# 05_-_PCIE_MINI_2_AUDIO2.net
KiCad netlist of a schematic drawn in Altium Designer
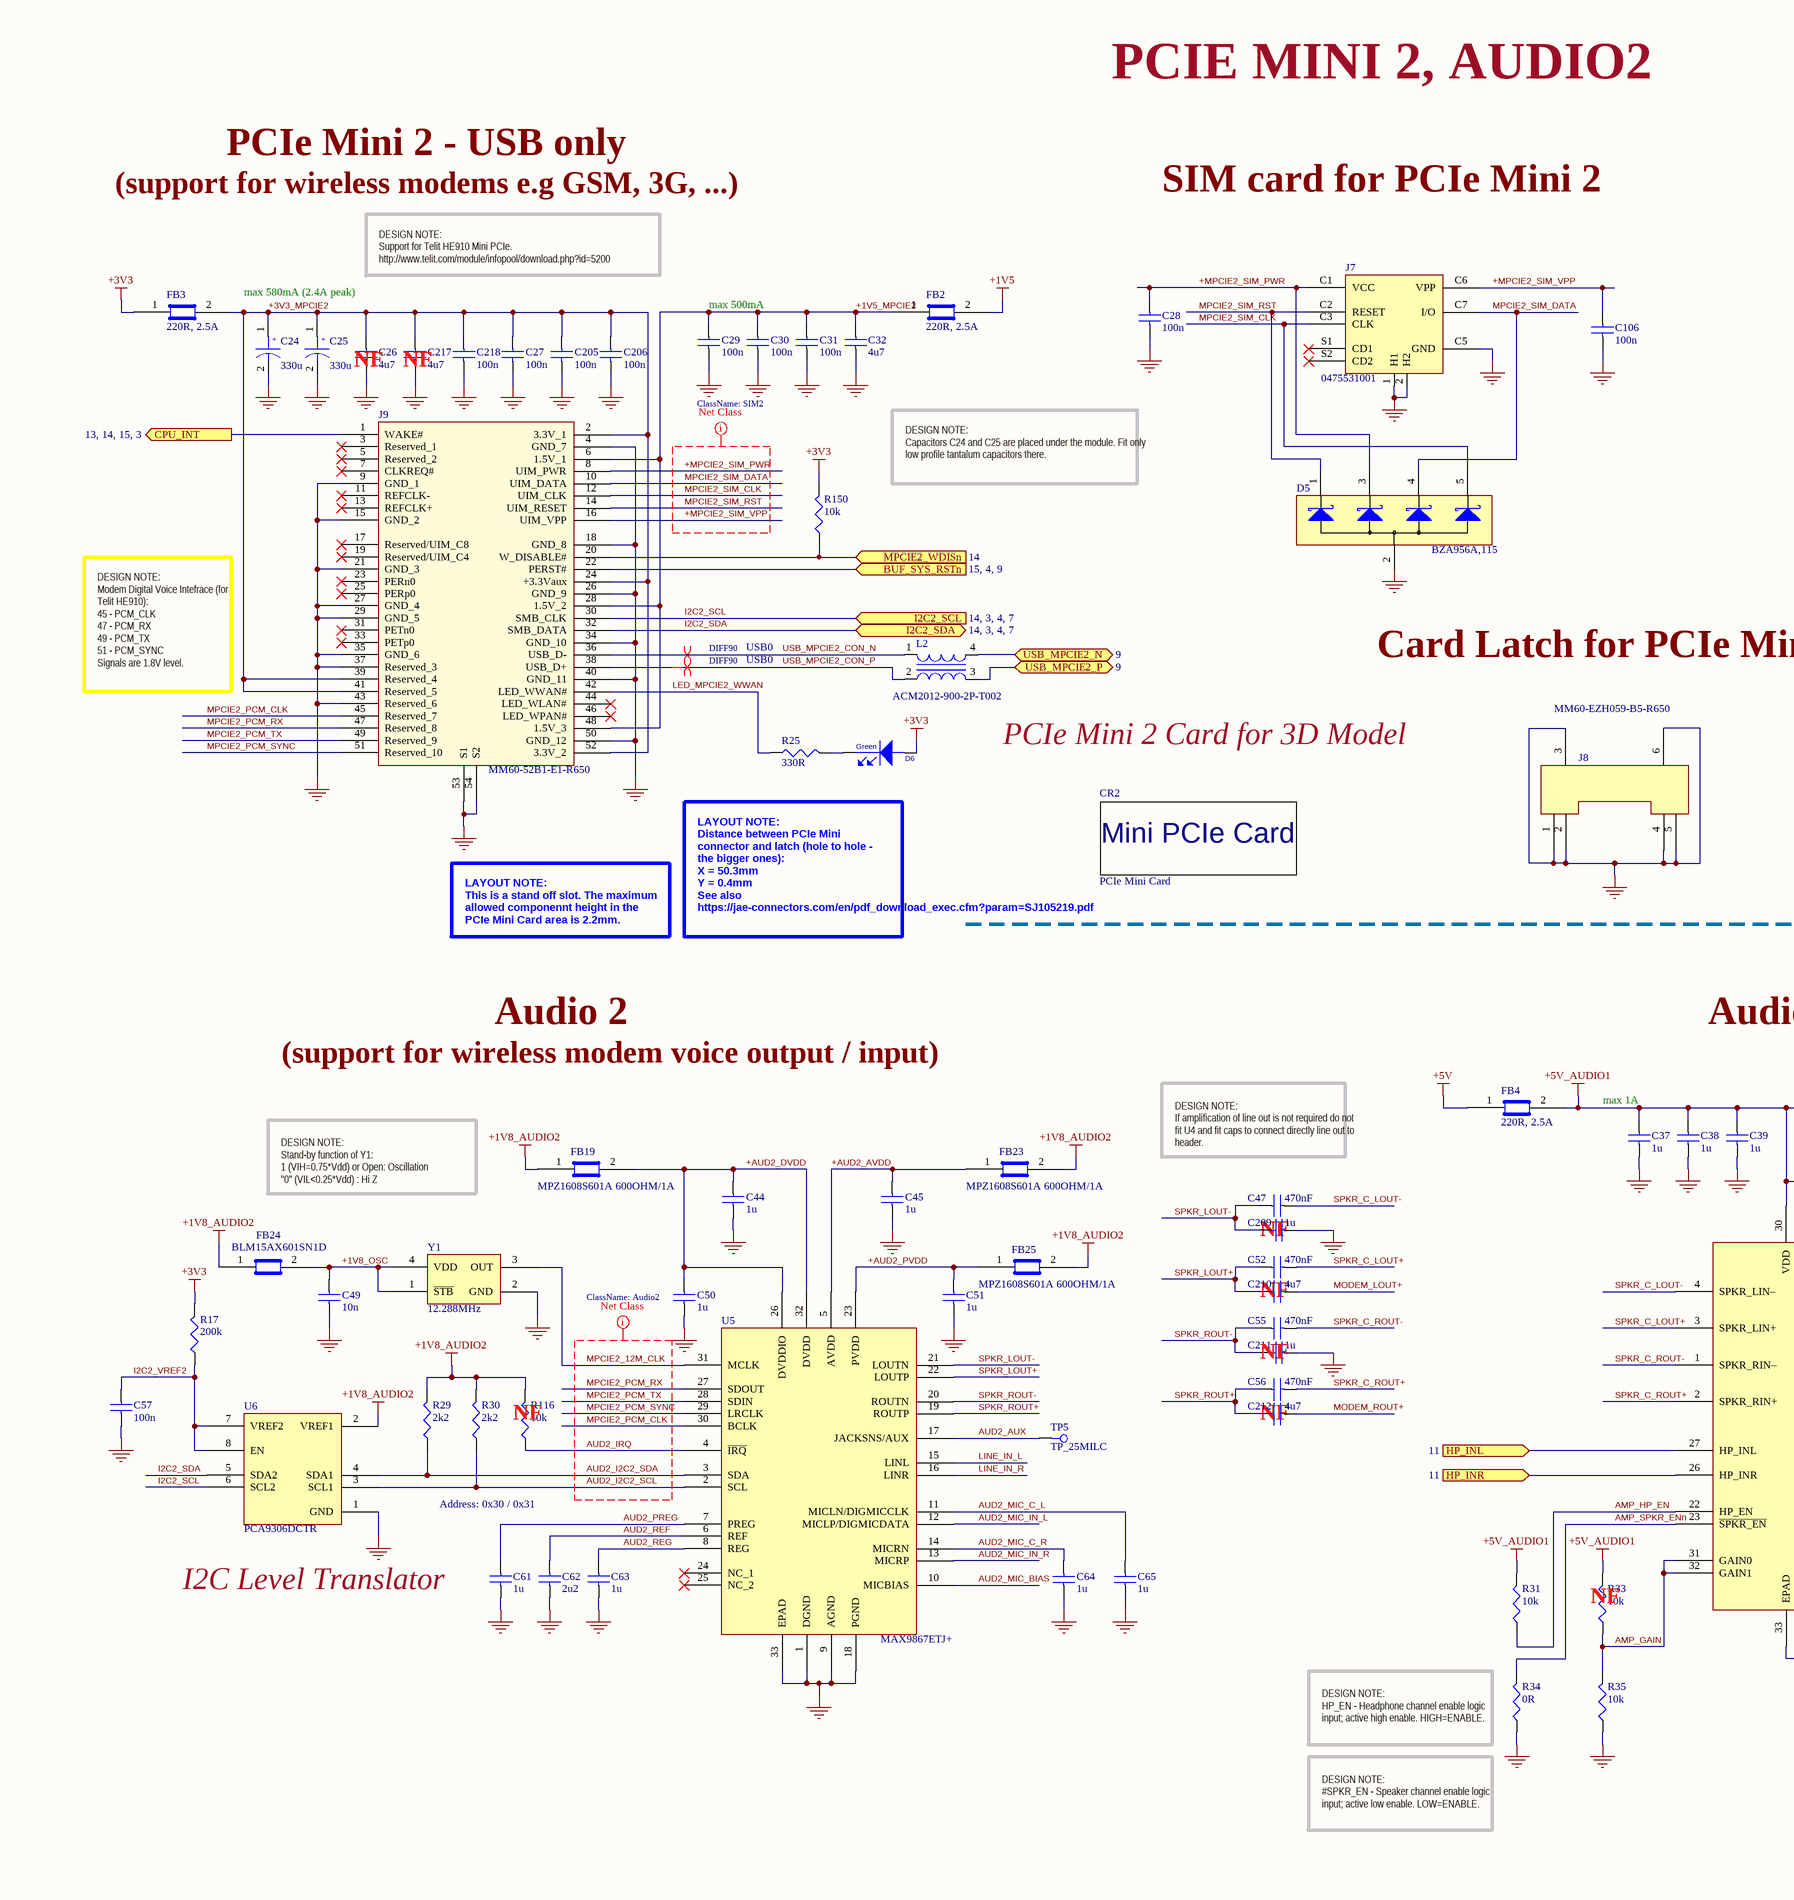
[diagram p0: [05] - PCIE MINI 2, AUDIO2.SchDoc, left]
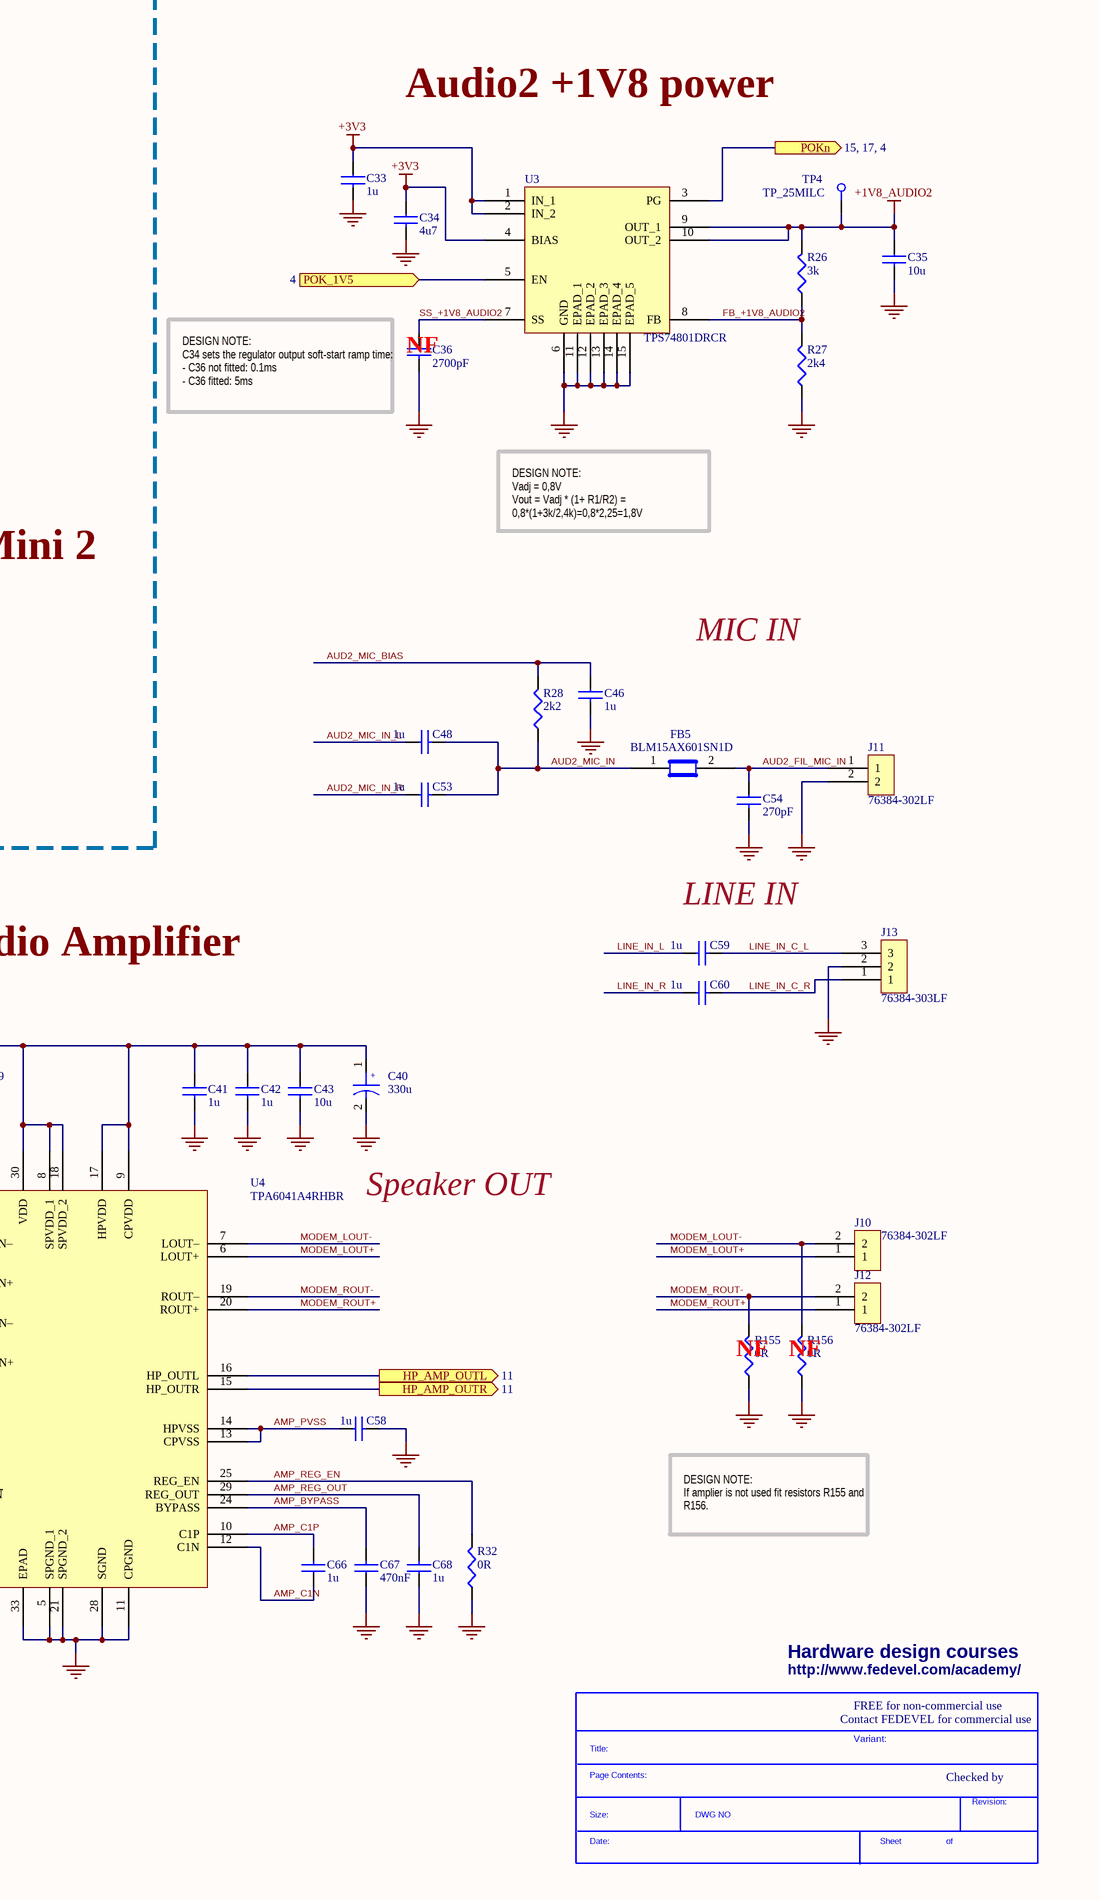
[diagram p1: [05] - PCIE MINI 2, AUDIO2.SchDoc, right]

(export (version "E")
  (design (tool "Eeschema 10.0.6"))
  (components
    (comp (ref "C24")
      (value "330u")
      (footprint "C2917")
      (description "CAP TANT 330UF 6.3V 20% 2917")
      (fields
        (field (name "MANUFACTURER") "Kemet")
        (field (name "MANUFACTURER PART NUMBER") "T520D337M006ATE045")
        (field (name ".CREATOR") "MM")
        (field (name ".CHECKED PCB") "MM")
        (field (name ".CHECKED SCH") "RF, used by MM")
      )
      (libsource (lib "Integrated_Library_RF_FEB_2012") (part "T520D337M006ATE045"))
    )
    (comp (ref "C25")
      (value "330u")
      (footprint "C2917")
      (description "CAP TANT 330UF 6.3V 20% 2917")
      (fields
        (field (name "MANUFACTURER") "Kemet")
        (field (name "MANUFACTURER PART NUMBER") "T520D337M006ATE045")
        (field (name ".CREATOR") "MM")
        (field (name ".CHECKED PCB") "MM")
        (field (name ".CHECKED SCH") "RF, used by MM")
      )
      (libsource (lib "Integrated_Library_RF_FEB_2012") (part "T520D337M006ATE045"))
    )
    (comp (ref "C26")
      (value "4u7")
      (footprint "C0402")
      (description "CAP CER 4.7UF 10V 20% X5R 0402")
      (fields
        (field (name "MANUFACTURER") "TDK Corporation")
        (field (name "MANUFACTURER PART NUMBER") "C1005X5R1A475M")
        (field (name ".CHECKED PCB") "RF")
        (field (name ".CHECKED SCH") "RF")
      )
      (libsource (lib "Integrated_Library_RF_FEB_2012") (part "C1005X5R1A475M"))
    )
    (comp (ref "C27")
      (value "100n")
      (footprint "C0402")
      (description "CAP CER .10UF 50V X5R 10% 0402")
      (fields
        (field (name "MANUFACTURER") "TDK Corporation")
        (field (name "MANUFACTURER PART NUMBER") "C1005X5R1H104K")
      )
      (libsource (lib "Integrated_Library_RF_FEB_2012") (part "C1005X5R1H104K"))
    )
    (comp (ref "C28")
      (value "100n")
      (footprint "C0402")
      (description "CAP CER .10UF 50V X5R 10% 0402")
      (fields
        (field (name "MANUFACTURER") "TDK Corporation")
        (field (name "MANUFACTURER PART NUMBER") "C1005X5R1H104K")
      )
      (libsource (lib "Integrated_Library_RF_FEB_2012") (part "C1005X5R1H104K"))
    )
    (comp (ref "C29")
      (value "100n")
      (footprint "C0402")
      (description "CAP CER .10UF 50V X5R 10% 0402")
      (fields
        (field (name "MANUFACTURER") "TDK Corporation")
        (field (name "MANUFACTURER PART NUMBER") "C1005X5R1H104K")
      )
      (libsource (lib "Integrated_Library_RF_FEB_2012") (part "C1005X5R1H104K"))
    )
    (comp (ref "C30")
      (value "100n")
      (footprint "C0402")
      (description "CAP CER .10UF 50V X5R 10% 0402")
      (fields
        (field (name "MANUFACTURER") "TDK Corporation")
        (field (name "MANUFACTURER PART NUMBER") "C1005X5R1H104K")
      )
      (libsource (lib "Integrated_Library_RF_FEB_2012") (part "C1005X5R1H104K"))
    )
    (comp (ref "C31")
      (value "100n")
      (footprint "C0402")
      (description "CAP CER .10UF 50V X5R 10% 0402")
      (fields
        (field (name "MANUFACTURER") "TDK Corporation")
        (field (name "MANUFACTURER PART NUMBER") "C1005X5R1H104K")
      )
      (libsource (lib "Integrated_Library_RF_FEB_2012") (part "C1005X5R1H104K"))
    )
    (comp (ref "C32")
      (value "4u7")
      (footprint "C0402")
      (description "CAP CER 4.7UF 10V 20% X5R 0402")
      (fields
        (field (name "MANUFACTURER") "TDK Corporation")
        (field (name "MANUFACTURER PART NUMBER") "C1005X5R1A475M")
        (field (name ".CHECKED PCB") "RF")
        (field (name ".CHECKED SCH") "RF")
      )
      (libsource (lib "Integrated_Library_RF_FEB_2012") (part "C1005X5R1A475M"))
    )
    (comp (ref "C33")
      (value "1u")
      (footprint "C0402")
      (description "CAP CER 1.0UF 16V X5R 0402")
      (fields
        (field (name "MANUFACTURER") "TDK Corporation")
        (field (name "MANUFACTURER PART NUMBER") "C1005X5R1C105K")
      )
      (libsource (lib "Integrated_Library_RF_FEB_2012") (part "C1005X5R1C105K"))
    )
    (comp (ref "C34")
      (value "4u7")
      (footprint "C0402")
      (description "CAP CER 4.7UF 10V 20% X5R 0402")
      (fields
        (field (name "MANUFACTURER") "TDK Corporation")
        (field (name "MANUFACTURER PART NUMBER") "C1005X5R1A475M")
        (field (name ".CHECKED PCB") "RF")
        (field (name ".CHECKED SCH") "RF")
      )
      (libsource (lib "Integrated_Library_RF_FEB_2012") (part "C1005X5R1A475M"))
    )
    (comp (ref "C35")
      (value "10u")
      (footprint "C0603")
      (description "CAP CER 10UF 6.3V X5R 20% 0603")
      (fields
        (field (name "MANUFACTURER") "TDK Corporation")
        (field (name "MANUFACTURER PART NUMBER") "C1608X5R0J106M")
      )
      (libsource (lib "Integrated_Library_RF_FEB_2012") (part "C1608X5R0J106M"))
    )
    (comp (ref "C36")
      (value "2700pF")
      (footprint "C0402")
      (description "CAP CER 2700PF 50V 10% X7R 0402")
      (fields
        (field (name "MANUFACTURER") "Murata Electronics North America")
        (field (name "MANUFACTURER PART NUMBER") "GRM155R71H272KA01D")
        (field (name ".CHECKED PCB") "RF")
        (field (name ".CHECKED SCH") "RF")
      )
      (libsource (lib "Integrated_Library_RF_FEB_2012") (part "GRM155R71H272KA01D"))
    )
    (comp (ref "C37")
      (value "1u")
      (footprint "C0402")
      (description "CAP CER 1.0UF 16V X5R 0402")
      (fields
        (field (name "MANUFACTURER") "TDK Corporation")
        (field (name "MANUFACTURER PART NUMBER") "C1005X5R1C105K")
      )
      (libsource (lib "Integrated_Library_RF_FEB_2012") (part "C1005X5R1C105K"))
    )
    (comp (ref "C38")
      (value "1u")
      (footprint "C0402")
      (description "CAP CER 1.0UF 16V X5R 0402")
      (fields
        (field (name "MANUFACTURER") "TDK Corporation")
        (field (name "MANUFACTURER PART NUMBER") "C1005X5R1C105K")
      )
      (libsource (lib "Integrated_Library_RF_FEB_2012") (part "C1005X5R1C105K"))
    )
    (comp (ref "C39")
      (value "1u")
      (footprint "C0402")
      (description "CAP CER 1.0UF 16V X5R 0402")
      (fields
        (field (name "MANUFACTURER") "TDK Corporation")
        (field (name "MANUFACTURER PART NUMBER") "C1005X5R1C105K")
      )
      (libsource (lib "Integrated_Library_RF_FEB_2012") (part "C1005X5R1C105K"))
    )
    (comp (ref "C40")
      (value "330u")
      (footprint "C2917")
      (description "CAP TANT 330UF 10V 10% 2917")
      (fields
        (field (name "MANUFACTURER") "Kemet")
        (field (name "MANUFACTURER PART NUMBER") "T495D337K010ATE150")
        (field (name ".CREATOR") "MM")
        (field (name ".CHECKED PCB") "MM")
        (field (name ".CHECKED SCH") "RF, used by MM")
      )
      (libsource (lib "Integrated_Library_RF_FEB_2012") (part "T495D337K010ATE150"))
    )
    (comp (ref "C41")
      (value "1u")
      (footprint "C0402")
      (description "CAP CER 1.0UF 16V X5R 0402")
      (fields
        (field (name "MANUFACTURER") "TDK Corporation")
        (field (name "MANUFACTURER PART NUMBER") "C1005X5R1C105K")
      )
      (libsource (lib "Integrated_Library_RF_FEB_2012") (part "C1005X5R1C105K"))
    )
    (comp (ref "C42")
      (value "1u")
      (footprint "C0402")
      (description "CAP CER 1.0UF 16V X5R 0402")
      (fields
        (field (name "MANUFACTURER") "TDK Corporation")
        (field (name "MANUFACTURER PART NUMBER") "C1005X5R1C105K")
      )
      (libsource (lib "Integrated_Library_RF_FEB_2012") (part "C1005X5R1C105K"))
    )
    (comp (ref "C43")
      (value "10u")
      (footprint "C0603")
      (description "CAP CER 10UF 6.3V X5R 20% 0603")
      (fields
        (field (name "MANUFACTURER") "TDK Corporation")
        (field (name "MANUFACTURER PART NUMBER") "C1608X5R0J106M")
      )
      (libsource (lib "Integrated_Library_RF_FEB_2012") (part "C1608X5R0J106M"))
    )
    (comp (ref "C44")
      (value "1u")
      (footprint "C0402")
      (description "CAP CER 1.0UF 16V X5R 0402")
      (fields
        (field (name "MANUFACTURER") "TDK Corporation")
        (field (name "MANUFACTURER PART NUMBER") "C1005X5R1C105K")
      )
      (libsource (lib "Integrated_Library_RF_FEB_2012") (part "C1005X5R1C105K"))
    )
    (comp (ref "C45")
      (value "1u")
      (footprint "C0402")
      (description "CAP CER 1.0UF 16V X5R 0402")
      (fields
        (field (name "MANUFACTURER") "TDK Corporation")
        (field (name "MANUFACTURER PART NUMBER") "C1005X5R1C105K")
      )
      (libsource (lib "Integrated_Library_RF_FEB_2012") (part "C1005X5R1C105K"))
    )
    (comp (ref "C46")
      (value "1u")
      (footprint "C0402")
      (description "CAP CER 1.0UF 16V X5R 0402")
      (fields
        (field (name "MANUFACTURER") "TDK Corporation")
        (field (name "MANUFACTURER PART NUMBER") "C1005X5R1C105K")
      )
      (libsource (lib "Integrated_Library_RF_FEB_2012") (part "C1005X5R1C105K"))
    )
    (comp (ref "C47")
      (value "470nF")
      (footprint "C0402")
      (description "CAP CER .47UF 16V X5R 0402")
      (fields
        (field (name "MANUFACTURER") "TDK Corporation")
        (field (name "MANUFACTURER PART NUMBER") "C1005X5R1C474K")
      )
      (libsource (lib "Integrated_Library_RF_FEB_2012") (part "C1005X5R1C474K"))
    )
    (comp (ref "C48")
      (value "1u")
      (footprint "C0402")
      (description "CAP CER 1.0UF 16V X5R 0402")
      (fields
        (field (name "MANUFACTURER") "TDK Corporation")
        (field (name "MANUFACTURER PART NUMBER") "C1005X5R1C105K")
      )
      (libsource (lib "Integrated_Library_RF_FEB_2012") (part "C1005X5R1C105K"))
    )
    (comp (ref "C49")
      (value "10n")
      (footprint "C0402")
      (description "CAP CER 10000PF 50V 10% X7R 0402")
      (fields
        (field (name "MANUFACTURER") "TDK Corporation")
        (field (name "MANUFACTURER PART NUMBER") "C1005X7R1H103K")
        (field (name ".CHECKED PCB") "RF")
        (field (name ".CHECKED SCH") "RF")
      )
      (libsource (lib "Integrated_Library_RF_FEB_2012") (part "C1005X7R1H103K"))
    )
    (comp (ref "C50")
      (value "1u")
      (footprint "C0402")
      (description "CAP CER 1.0UF 16V X5R 0402")
      (fields
        (field (name "MANUFACTURER") "TDK Corporation")
        (field (name "MANUFACTURER PART NUMBER") "C1005X5R1C105K")
      )
      (libsource (lib "Integrated_Library_RF_FEB_2012") (part "C1005X5R1C105K"))
    )
    (comp (ref "C51")
      (value "1u")
      (footprint "C0402")
      (description "CAP CER 1.0UF 16V X5R 0402")
      (fields
        (field (name "MANUFACTURER") "TDK Corporation")
        (field (name "MANUFACTURER PART NUMBER") "C1005X5R1C105K")
      )
      (libsource (lib "Integrated_Library_RF_FEB_2012") (part "C1005X5R1C105K"))
    )
    (comp (ref "C52")
      (value "470nF")
      (footprint "C0402")
      (description "CAP CER .47UF 16V X5R 0402")
      (fields
        (field (name "MANUFACTURER") "TDK Corporation")
        (field (name "MANUFACTURER PART NUMBER") "C1005X5R1C474K")
      )
      (libsource (lib "Integrated_Library_RF_FEB_2012") (part "C1005X5R1C474K"))
    )
    (comp (ref "C53")
      (value "1u")
      (footprint "C0402")
      (description "CAP CER 1.0UF 16V X5R 0402")
      (fields
        (field (name "MANUFACTURER") "TDK Corporation")
        (field (name "MANUFACTURER PART NUMBER") "C1005X5R1C105K")
      )
      (libsource (lib "Integrated_Library_RF_FEB_2012") (part "C1005X5R1C105K"))
    )
    (comp (ref "C54")
      (value "270pF")
      (footprint "C0402")
      (description "CAP CER 270PF 50V 10% X7R 0402")
      (fields
        (field (name "MANUFACTURER") "Murata Electronics North America")
        (field (name "MANUFACTURER PART NUMBER") "GRM155R71H271KA01D")
        (field (name ".CHECKED PCB") "RF")
        (field (name ".CHECKED SCH") "RF")
      )
      (libsource (lib "Integrated_Library_RF_FEB_2012") (part "GRM155R71H271KA01D"))
    )
    (comp (ref "C55")
      (value "470nF")
      (footprint "C0402")
      (description "CAP CER .47UF 16V X5R 0402")
      (fields
        (field (name "MANUFACTURER") "TDK Corporation")
        (field (name "MANUFACTURER PART NUMBER") "C1005X5R1C474K")
      )
      (libsource (lib "Integrated_Library_RF_FEB_2012") (part "C1005X5R1C474K"))
    )
    (comp (ref "C56")
      (value "470nF")
      (footprint "C0402")
      (description "CAP CER .47UF 16V X5R 0402")
      (fields
        (field (name "MANUFACTURER") "TDK Corporation")
        (field (name "MANUFACTURER PART NUMBER") "C1005X5R1C474K")
      )
      (libsource (lib "Integrated_Library_RF_FEB_2012") (part "C1005X5R1C474K"))
    )
    (comp (ref "C57")
      (value "100n")
      (footprint "C0402")
      (description "CAP CER .10UF 50V X5R 10% 0402")
      (fields
        (field (name "MANUFACTURER") "TDK Corporation")
        (field (name "MANUFACTURER PART NUMBER") "C1005X5R1H104K")
      )
      (libsource (lib "Integrated_Library_RF_FEB_2012") (part "C1005X5R1H104K"))
    )
    (comp (ref "C58")
      (value "1u")
      (footprint "C0402")
      (description "CAP CER 1.0UF 16V X5R 0402")
      (fields
        (field (name "MANUFACTURER") "TDK Corporation")
        (field (name "MANUFACTURER PART NUMBER") "C1005X5R1C105K")
      )
      (libsource (lib "Integrated_Library_RF_FEB_2012") (part "C1005X5R1C105K"))
    )
    (comp (ref "C59")
      (value "1u")
      (footprint "C0402")
      (description "CAP CER 1.0UF 16V X5R 0402")
      (fields
        (field (name "MANUFACTURER") "TDK Corporation")
        (field (name "MANUFACTURER PART NUMBER") "C1005X5R1C105K")
      )
      (libsource (lib "Integrated_Library_RF_FEB_2012") (part "C1005X5R1C105K"))
    )
    (comp (ref "C60")
      (value "1u")
      (footprint "C0402")
      (description "CAP CER 1.0UF 16V X5R 0402")
      (fields
        (field (name "MANUFACTURER") "TDK Corporation")
        (field (name "MANUFACTURER PART NUMBER") "C1005X5R1C105K")
      )
      (libsource (lib "Integrated_Library_RF_FEB_2012") (part "C1005X5R1C105K"))
    )
    (comp (ref "C61")
      (value "1u")
      (footprint "C0402")
      (description "CAP CER 1.0UF 16V X5R 0402")
      (fields
        (field (name "MANUFACTURER") "TDK Corporation")
        (field (name "MANUFACTURER PART NUMBER") "C1005X5R1C105K")
      )
      (libsource (lib "Integrated_Library_RF_FEB_2012") (part "C1005X5R1C105K"))
    )
    (comp (ref "C62")
      (value "2u2")
      (footprint "C0402")
      (description "CAP CER 2.2UF 10V 10% X5R 0402")
      (fields
        (field (name "MANUFACTURER") "TDK Corporation")
        (field (name "MANUFACTURER PART NUMBER") "C1005X5R1A225K")
        (field (name ".CHECKED PCB") "RF")
        (field (name ".CHECKED SCH") "RF")
      )
      (libsource (lib "Integrated_Library_RF_FEB_2012") (part "C1005X5R1A225K"))
    )
    (comp (ref "C63")
      (value "1u")
      (footprint "C0402")
      (description "CAP CER 1.0UF 16V X5R 0402")
      (fields
        (field (name "MANUFACTURER") "TDK Corporation")
        (field (name "MANUFACTURER PART NUMBER") "C1005X5R1C105K")
      )
      (libsource (lib "Integrated_Library_RF_FEB_2012") (part "C1005X5R1C105K"))
    )
    (comp (ref "C64")
      (value "1u")
      (footprint "C0402")
      (description "CAP CER 1.0UF 16V X5R 0402")
      (fields
        (field (name "MANUFACTURER") "TDK Corporation")
        (field (name "MANUFACTURER PART NUMBER") "C1005X5R1C105K")
      )
      (libsource (lib "Integrated_Library_RF_FEB_2012") (part "C1005X5R1C105K"))
    )
    (comp (ref "C65")
      (value "1u")
      (footprint "C0402")
      (description "CAP CER 1.0UF 16V X5R 0402")
      (fields
        (field (name "MANUFACTURER") "TDK Corporation")
        (field (name "MANUFACTURER PART NUMBER") "C1005X5R1C105K")
      )
      (libsource (lib "Integrated_Library_RF_FEB_2012") (part "C1005X5R1C105K"))
    )
    (comp (ref "C66")
      (value "1u")
      (footprint "C0402")
      (description "CAP CER 1.0UF 16V X5R 0402")
      (fields
        (field (name "MANUFACTURER") "TDK Corporation")
        (field (name "MANUFACTURER PART NUMBER") "C1005X5R1C105K")
      )
      (libsource (lib "Integrated_Library_RF_FEB_2012") (part "C1005X5R1C105K"))
    )
    (comp (ref "C67")
      (value "470nF")
      (footprint "C0402")
      (description "CAP CER .47UF 16V X5R 0402")
      (fields
        (field (name "MANUFACTURER") "TDK Corporation")
        (field (name "MANUFACTURER PART NUMBER") "C1005X5R1C474K")
      )
      (libsource (lib "Integrated_Library_RF_FEB_2012") (part "C1005X5R1C474K"))
    )
    (comp (ref "C68")
      (value "1u")
      (footprint "C0402")
      (description "CAP CER 1.0UF 16V X5R 0402")
      (fields
        (field (name "MANUFACTURER") "TDK Corporation")
        (field (name "MANUFACTURER PART NUMBER") "C1005X5R1C105K")
      )
      (libsource (lib "Integrated_Library_RF_FEB_2012") (part "C1005X5R1C105K"))
    )
    (comp (ref "C106")
      (value "100n")
      (footprint "C0402")
      (description "CAP CER .10UF 50V X5R 10% 0402")
      (fields
        (field (name "MANUFACTURER") "TDK Corporation")
        (field (name "MANUFACTURER PART NUMBER") "C1005X5R1H104K")
      )
      (libsource (lib "Integrated_Library_RF_FEB_2012") (part "C1005X5R1H104K"))
    )
    (comp (ref "C205")
      (value "100n")
      (footprint "C0402")
      (description "CAP CER .10UF 50V X5R 10% 0402")
      (fields
        (field (name "MANUFACTURER") "TDK Corporation")
        (field (name "MANUFACTURER PART NUMBER") "C1005X5R1H104K")
      )
      (libsource (lib "Integrated_Library_RF_FEB_2012") (part "C1005X5R1H104K"))
    )
    (comp (ref "C206")
      (value "100n")
      (footprint "C0402")
      (description "CAP CER .10UF 50V X5R 10% 0402")
      (fields
        (field (name "MANUFACTURER") "TDK Corporation")
        (field (name "MANUFACTURER PART NUMBER") "C1005X5R1H104K")
      )
      (libsource (lib "Integrated_Library_RF_FEB_2012") (part "C1005X5R1H104K"))
    )
    (comp (ref "C209")
      (value "1u")
      (footprint "C0402")
      (description "CAP CER 1.0UF 16V X5R 0402")
      (fields
        (field (name "MANUFACTURER") "TDK Corporation")
        (field (name "MANUFACTURER PART NUMBER") "C1005X5R1C105K")
      )
      (libsource (lib "Integrated_Library_RF_FEB_2012") (part "C1005X5R1C105K"))
    )
    (comp (ref "C210")
      (value "4u7")
      (footprint "C0402")
      (description "CAP CER 4.7UF 10V 20% X5R 0402")
      (fields
        (field (name "MANUFACTURER") "TDK Corporation")
        (field (name "MANUFACTURER PART NUMBER") "C1005X5R1A475M")
        (field (name ".CHECKED PCB") "RF")
        (field (name ".CHECKED SCH") "RF")
      )
      (libsource (lib "Integrated_Library_RF_FEB_2012") (part "C1005X5R1A475M"))
    )
    (comp (ref "C211")
      (value "1u")
      (footprint "C0402")
      (description "CAP CER 1.0UF 16V X5R 0402")
      (fields
        (field (name "MANUFACTURER") "TDK Corporation")
        (field (name "MANUFACTURER PART NUMBER") "C1005X5R1C105K")
      )
      (libsource (lib "Integrated_Library_RF_FEB_2012") (part "C1005X5R1C105K"))
    )
    (comp (ref "C212")
      (value "4u7")
      (footprint "C0402")
      (description "CAP CER 4.7UF 10V 20% X5R 0402")
      (fields
        (field (name "MANUFACTURER") "TDK Corporation")
        (field (name "MANUFACTURER PART NUMBER") "C1005X5R1A475M")
        (field (name ".CHECKED PCB") "RF")
        (field (name ".CHECKED SCH") "RF")
      )
      (libsource (lib "Integrated_Library_RF_FEB_2012") (part "C1005X5R1A475M"))
    )
    (comp (ref "C217")
      (value "4u7")
      (footprint "C0402")
      (description "CAP CER 4.7UF 10V 20% X5R 0402")
      (fields
        (field (name "MANUFACTURER") "TDK Corporation")
        (field (name "MANUFACTURER PART NUMBER") "C1005X5R1A475M")
        (field (name ".CHECKED PCB") "RF")
        (field (name ".CHECKED SCH") "RF")
      )
      (libsource (lib "Integrated_Library_RF_FEB_2012") (part "C1005X5R1A475M"))
    )
    (comp (ref "C218")
      (value "100n")
      (footprint "C0402")
      (description "CAP CER .10UF 50V X5R 10% 0402")
      (fields
        (field (name "MANUFACTURER") "TDK Corporation")
        (field (name "MANUFACTURER PART NUMBER") "C1005X5R1H104K")
      )
      (libsource (lib "Integrated_Library_RF_FEB_2012") (part "C1005X5R1H104K"))
    )
    (comp (ref "CR2")
      (value "PCIe Mini Card")
      (footprint "Mini_PCIe_full card")
      (description "Card MIni PCIe")
      (fields (field (name ".CREATOR") "MM"))
      (libsource (lib "Integrated_Library_RF_FEB_2012") (part "Card_Mini_PCIe"))
    )
    (comp (ref "D5")
      (value "BZA956A,115")
      (footprint "SOT665")
      (description "TVS ZENER QUAD 5.6V SOT665")
      (fields
        (field (name "MANUFACTURER") "NXP Semiconductors")
        (field (name ".CREATOR") "MM")
        (field (name ".CHECKED PCB") "MM")
        (field (name ".CHECKED SCH") "MM")
      )
      (libsource (lib "Integrated_Library_RF_FEB_2012") (part "BZA956A,115"))
    )
    (comp (ref "D6")
      (value "Green")
      (footprint "LED_0603")
      (description "LED SMARTLED GREEN 570NM 0603")
      (fields
        (field (name "MANUFACTURER") "OSRAM Opto Semiconductors Inc")
        (field (name "MANUFACTURER PART NUMBER") "LG L29K-G2J1-24-Z")
      )
      (libsource (lib "Integrated_Library_RF_FEB_2012") (part "LG L29K-G2J1-24-Z"))
    )
    (comp (ref "FB2")
      (value "220R, 2.5A")
      (footprint "C0603")
      (description "FERRITE CHIP 220 OHM 2500MA 0603")
      (fields
        (field (name "MANUFACTURER") "Murata Electronics North America")
        (field (name "MANUFACTURER PART NUMBER") "BLM18SG221TN1D")
        (field (name ".CHECKED PCB") "RF")
        (field (name ".CHECKED SCH") "RF")
      )
      (libsource (lib "Integrated_Library_RF_FEB_2012") (part "BLM18SG221TN1D"))
    )
    (comp (ref "FB3")
      (value "220R, 2.5A")
      (footprint "C0603")
      (description "FERRITE CHIP 220 OHM 2500MA 0603")
      (fields
        (field (name "MANUFACTURER") "Murata Electronics North America")
        (field (name "MANUFACTURER PART NUMBER") "BLM18SG221TN1D")
        (field (name ".CHECKED PCB") "RF")
        (field (name ".CHECKED SCH") "RF")
      )
      (libsource (lib "Integrated_Library_RF_FEB_2012") (part "BLM18SG221TN1D"))
    )
    (comp (ref "FB4")
      (value "220R, 2.5A")
      (footprint "C0603")
      (description "FERRITE CHIP 220 OHM 2500MA 0603")
      (fields
        (field (name "MANUFACTURER") "Murata Electronics North America")
        (field (name "MANUFACTURER PART NUMBER") "BLM18SG221TN1D")
        (field (name ".CHECKED PCB") "RF")
        (field (name ".CHECKED SCH") "RF")
      )
      (libsource (lib "Integrated_Library_RF_FEB_2012") (part "BLM18SG221TN1D"))
    )
    (comp (ref "FB5")
      (value "BLM15AX601SN1D")
      (footprint "C0402")
      (description "FERRITE CHIP 600 OHM 0402")
      (fields (field (name "MANUFACTURER") "Murata Electronics North America"))
      (libsource (lib "Integrated_Library_RF_FEB_2012") (part "BLM15AX601SN1D"))
    )
    (comp (ref "FB19")
      (value "MPZ1608S601A 600OHM/1A")
      (footprint "C0603")
      (description "FERRITE CHIP BEAD 600 OHM SMD 1A")
      (fields
        (field (name "MANUFACTURER") "TDK Corporation")
        (field (name "MANUFACTURER PART NUMBER") "MPZ1608S601A")
        (field (name ".CHECKED PCB") "RF")
        (field (name ".CHECKED SCH") "RF")
      )
      (libsource (lib "Integrated_Library_RF_FEB_2012") (part "MPZ1608S601A"))
    )
    (comp (ref "FB23")
      (value "MPZ1608S601A 600OHM/1A")
      (footprint "C0603")
      (description "FERRITE CHIP BEAD 600 OHM SMD 1A")
      (fields
        (field (name "MANUFACTURER") "TDK Corporation")
        (field (name "MANUFACTURER PART NUMBER") "MPZ1608S601A")
        (field (name ".CHECKED PCB") "RF")
        (field (name ".CHECKED SCH") "RF")
      )
      (libsource (lib "Integrated_Library_RF_FEB_2012") (part "MPZ1608S601A"))
    )
    (comp (ref "FB24")
      (value "BLM15AX601SN1D")
      (footprint "C0402")
      (description "FERRITE CHIP 600 OHM 0402")
      (fields (field (name "MANUFACTURER") "Murata Electronics North America"))
      (libsource (lib "Integrated_Library_RF_FEB_2012") (part "BLM15AX601SN1D"))
    )
    (comp (ref "FB25")
      (value "MPZ1608S601A 600OHM/1A")
      (footprint "C0603")
      (description "FERRITE CHIP BEAD 600 OHM SMD 1A")
      (fields
        (field (name "MANUFACTURER") "TDK Corporation")
        (field (name "MANUFACTURER PART NUMBER") "MPZ1608S601A")
        (field (name ".CHECKED PCB") "RF")
        (field (name ".CHECKED SCH") "RF")
      )
      (libsource (lib "Integrated_Library_RF_FEB_2012") (part "MPZ1608S601A"))
    )
    (comp (ref "J7")
      (value "0475531001")
      (footprint "SIM_CARD_PUSH")
      (description "CONN CARD HOLDER SIM 6POS SMD")
      (fields
        (field (name "MANUFACTURER") "Molex Inc")
        (field (name ".CREATOR") "MM")
        (field (name ".CHECKED PCB") "MM")
        (field (name ".CHECKED SCH") "MM")
      )
      (libsource (lib "Integrated_Library_RF_FEB_2012") (part "0475531001"))
    )
    (comp (ref "J8")
      (value "MM60-EZH059-B5-R650")
      (footprint "MINI_PCIE_52PIN_CARD_LATCH")
      (description "CONN MINI EXPRESS CARD LATCH SMD")
      (fields
        (field (name "MANUFACTURER") "JAE Electronics")
        (field (name ".CREATOR") "MM")
        (field (name ".CHECKED PCB") "MM")
        (field (name ".CHECKED SCH") "MM")
      )
      (libsource (lib "Integrated_Library_RF_FEB_2012") (part "MM60-EZH059-B5-R650"))
    )
    (comp (ref "J9")
      (value "MM60-52B1-E1-R650")
      (footprint "MINI_PCIE_52PIN_CARD_CON")
      (description "CONN MINI EXPRESS CARD 52POS SMD")
      (fields
        (field (name "MANUFACTURER") "JAE Electronics")
        (field (name ".CREATOR") "MM")
        (field (name ".CHECKED PCB") "MM")
        (field (name ".CHECKED SCH") "MM")
      )
      (libsource (lib "Integrated_Library_RF_FEB_2012") (part "MM60-52B1-E1-R650"))
    )
    (comp (ref "J10")
      (value "76384-302LF")
      (footprint "HDR_1x2_2.54MM_SHDR")
      (description "CONN HEADER 2POS .100\" STR GOLD")
      (fields
        (field (name "MANUFACTURER") "FCI")
        (field (name ".CREATOR") "MM")
        (field (name ".CHECKED PCB") "MM")
        (field (name ".CHECKED SCH") "MM")
      )
      (libsource (lib "Integrated_Library_RF_FEB_2012") (part "76384-302LF"))
    )
    (comp (ref "J11")
      (value "76384-302LF")
      (footprint "HDR_1x2_2.54MM_SHDR")
      (description "CONN HEADER 2POS .100\" STR GOLD")
      (fields
        (field (name "MANUFACTURER") "FCI")
        (field (name ".CREATOR") "MM")
        (field (name ".CHECKED PCB") "MM")
        (field (name ".CHECKED SCH") "MM")
      )
      (libsource (lib "") (part "76384-302LF_1"))
    )
    (comp (ref "J12")
      (value "76384-302LF")
      (footprint "HDR_1x2_2.54MM_SHDR")
      (description "CONN HEADER 2POS .100\" STR GOLD")
      (fields
        (field (name "MANUFACTURER") "FCI")
        (field (name ".CREATOR") "MM")
        (field (name ".CHECKED PCB") "MM")
        (field (name ".CHECKED SCH") "MM")
      )
      (libsource (lib "Integrated_Library_RF_FEB_2012") (part "76384-302LF"))
    )
    (comp (ref "J13")
      (value "76384-303LF")
      (footprint "HDR_1x3_2.54MM_SHDR_V2")
      (description "CONN HEADER 3POS .100\" STR GOLD")
      (fields
        (field (name "MANUFACTURER") "FCI")
        (field (name ".CREATOR") "MM")
        (field (name ".CHECKED PCB") "MM")
        (field (name ".CHECKED SCH") "MM")
      )
      (libsource (lib "Integrated_Library_RF_FEB_2012") (part "76384-303LF"))
    )
    (comp (ref "L2")
      (value "ACM2012-900-2P-T002")
      (footprint "ACM2012")
      (description "CHOKE COMM MODE 90 OHM .4A SMD")
      (fields
        (field (name "MANUFACTURER") "TDK Corporation")
        (field (name "TOLERANCE") "±1%")
        (field (name ".CHECKED PCB") "RF")
        (field (name ".CHECKED SCH") "RF")
      )
      (libsource (lib "Integrated_Library_RF_FEB_2012") (part "ACM2012-900-2P-T002"))
    )
    (comp (ref "R17")
      (value "200k")
      (footprint "R0402")
      (description "RES 200K OHM 1/16W 1% 0402 SMD")
      (fields
        (field (name "MANUFACTURER") "Yageo")
        (field (name "MANUFACTURER PART NUMBER") "RC0402FR-07200KL")
      )
      (libsource (lib "Integrated_Library_RF_FEB_2012") (part "RC0402FR-07200KL"))
    )
    (comp (ref "R25")
      (value "330R")
      (footprint "R0402")
      (description "RES 330 OHM 1/16W 1% 0402 SMD")
      (fields
        (field (name "MANUFACTURER") "Vishay Dale")
        (field (name "MANUFACTURER PART NUMBER") "CRCW0402330RFKED")
        (field (name ".CHECKED PCB") "RF")
        (field (name ".CHECKED SCH") "RF")
      )
      (libsource (lib "Integrated_Library_RF_FEB_2012") (part "CRCW0402330RFKED"))
    )
    (comp (ref "R26")
      (value "3k")
      (footprint "R0402")
      (description "RES 3K OHM 1/16W 1% 0402 SMD")
      (fields
        (field (name "MANUFACTURER") "Yageo")
        (field (name "MANUFACTURER PART NUMBER") "RC0402FR-073KL")
        (field (name ".CREATOR") "MM")
        (field (name ".CHECKED SCH") "RF, used by MM")
        (field (name ".CHECKED PCB") "RF, used by MM")
      )
      (libsource (lib "Integrated_Library_RF_FEB_2012") (part "RC0402FR-073KL"))
    )
    (comp (ref "R27")
      (value "2k4")
      (footprint "R0402")
      (description "RES 2.40K OHM 1/16W 1% 0402 SMD")
      (fields
        (field (name "MANUFACTURER") "Vishay Dale")
        (field (name "MANUFACTURER PART NUMBER") "CRCW04022K40FKED")
        (field (name ".CHECKED PCB") "RF")
        (field (name ".CHECKED SCH") "RF")
      )
      (libsource (lib "Integrated_Library_RF_FEB_2012") (part "CRCW04022K40FKED"))
    )
    (comp (ref "R28")
      (value "2k2")
      (footprint "R0402")
      (description "RES 2.20K OHM 1/16W 1% 0402 SMD")
      (fields
        (field (name "MANUFACTURER") "Yageo")
        (field (name "MANUFACTURER PART NUMBER") "RC0402FR-072K2L")
      )
      (libsource (lib "Integrated_Library_RF_FEB_2012") (part "RC0402FR-072K2L"))
    )
    (comp (ref "R29")
      (value "2k2")
      (footprint "R0402")
      (description "RES 2.20K OHM 1/16W 1% 0402 SMD")
      (fields
        (field (name "MANUFACTURER") "Yageo")
        (field (name "MANUFACTURER PART NUMBER") "RC0402FR-072K2L")
      )
      (libsource (lib "Integrated_Library_RF_FEB_2012") (part "RC0402FR-072K2L"))
    )
    (comp (ref "R30")
      (value "2k2")
      (footprint "R0402")
      (description "RES 2.20K OHM 1/16W 1% 0402 SMD")
      (fields
        (field (name "MANUFACTURER") "Yageo")
        (field (name "MANUFACTURER PART NUMBER") "RC0402FR-072K2L")
      )
      (libsource (lib "Integrated_Library_RF_FEB_2012") (part "RC0402FR-072K2L"))
    )
    (comp (ref "R31")
      (value "10k")
      (footprint "R0402")
      (description "RES 10.0K OHM 1/16W 1% 0402 SMD")
      (fields
        (field (name "MANUFACTURER") "Yageo")
        (field (name "MANUFACTURER PART NUMBER") "RC0402FR-0710KL")
      )
      (libsource (lib "Integrated_Library_RF_FEB_2012") (part "RC0402FR-0710KL"))
    )
    (comp (ref "R32")
      (value "0R")
      (footprint "R0402")
      (description "RES 0.0 OHM 1/16W 0402 SMD")
      (fields
        (field (name "MANUFACTURER") "Yageo")
        (field (name "MANUFACTURER PART NUMBER") "RC0402JR-070RL")
      )
      (libsource (lib "Integrated_Library_RF_FEB_2012") (part "RC0402JR-070RL"))
    )
    (comp (ref "R33")
      (value "10k")
      (footprint "R0402")
      (description "RES 10.0K OHM 1/16W 1% 0402 SMD")
      (fields
        (field (name "MANUFACTURER") "Yageo")
        (field (name "MANUFACTURER PART NUMBER") "RC0402FR-0710KL")
      )
      (libsource (lib "Integrated_Library_RF_FEB_2012") (part "RC0402FR-0710KL"))
    )
    (comp (ref "R34")
      (value "0R")
      (footprint "R0402")
      (description "RES 0.0 OHM 1/16W 0402 SMD")
      (fields
        (field (name "MANUFACTURER") "Yageo")
        (field (name "MANUFACTURER PART NUMBER") "RC0402JR-070RL")
      )
      (libsource (lib "Integrated_Library_RF_FEB_2012") (part "RC0402JR-070RL"))
    )
    (comp (ref "R35")
      (value "10k")
      (footprint "R0402")
      (description "RES 10.0K OHM 1/16W 1% 0402 SMD")
      (fields
        (field (name "MANUFACTURER") "Yageo")
        (field (name "MANUFACTURER PART NUMBER") "RC0402FR-0710KL")
      )
      (libsource (lib "Integrated_Library_RF_FEB_2012") (part "RC0402FR-0710KL"))
    )
    (comp (ref "R116")
      (value "10k")
      (footprint "R0402")
      (description "RES 10.0K OHM 1/16W 1% 0402 SMD")
      (fields
        (field (name "MANUFACTURER") "Yageo")
        (field (name "MANUFACTURER PART NUMBER") "RC0402FR-0710KL")
      )
      (libsource (lib "Integrated_Library_RF_FEB_2012") (part "RC0402FR-0710KL"))
    )
    (comp (ref "R150")
      (value "10k")
      (footprint "R0402")
      (description "RES 10.0K OHM 1/16W 1% 0402 SMD")
      (fields
        (field (name "MANUFACTURER") "Yageo")
        (field (name "MANUFACTURER PART NUMBER") "RC0402FR-0710KL")
      )
      (libsource (lib "Integrated_Library_RF_FEB_2012") (part "RC0402FR-0710KL"))
    )
    (comp (ref "R155")
      (value "0R")
      (footprint "R0402")
      (description "RES 0.0 OHM 1/16W 0402 SMD")
      (fields
        (field (name "MANUFACTURER") "Yageo")
        (field (name "MANUFACTURER PART NUMBER") "RC0402JR-070RL")
      )
      (libsource (lib "Integrated_Library_RF_FEB_2012") (part "RC0402JR-070RL"))
    )
    (comp (ref "R156")
      (value "0R")
      (footprint "R0402")
      (description "RES 0.0 OHM 1/16W 0402 SMD")
      (fields
        (field (name "MANUFACTURER") "Yageo")
        (field (name "MANUFACTURER PART NUMBER") "RC0402JR-070RL")
      )
      (libsource (lib "Integrated_Library_RF_FEB_2012") (part "RC0402JR-070RL"))
    )
    (comp (ref "TP4")
      (value "TP_25MILC")
      (footprint "TP_25C")
      (description "Test Point 25mil")
      (libsource (lib "Integrated_Library_RF_FEB_2012") (part "TP_25MILC"))
    )
    (comp (ref "TP5")
      (value "TP_25MILC")
      (footprint "TP_25C")
      (description "Test Point 25mil")
      (libsource (lib "Integrated_Library_RF_FEB_2012") (part "TP_25MILC"))
    )
    (comp (ref "U3")
      (value "TPS74801DRCR")
      (footprint "DRC (S-PVSON-N10)")
      (description "IC REG LDO ADJ 1.5A 10SON")
      (fields
        (field (name "MANUFACTURER") "Texas Instruments")
        (field (name ".CREATOR") "MM")
        (field (name ".CHECKED PCB") "RF, used by MM")
        (field (name ".CHECKED SCH") "MM")
      )
      (libsource (lib "Integrated_Library_RF_FEB_2012") (part "TPS74801DRCR"))
    )
    (comp (ref "U4")
      (value "TPA6041A4RHBR")
      (footprint "VQFN32 5x5x0.85")
      (description "IC AMP AUDIO PWR 2.6W AB 32VQFN")
      (fields
        (field (name "MANUFACTURER") "Texas Instruments")
        (field (name ".CREATOR") "MM")
        (field (name ".CHECKED PCB") "MM")
        (field (name ".CHECKED SCH") "MM")
      )
      (libsource (lib "Integrated_Library_RF_FEB_2012") (part "TPA6041A4RHBR"))
    )
    (comp (ref "U5")
      (value "MAX9867ETJ+")
      (footprint "QFN32 5x5x0.85")
      (description "IC STEREO AUD CODEC LP 32TQFN-EP")
      (fields
        (field (name "MANUFACTURER") "Maxim Integrated")
        (field (name ".CREATOR") "MM")
        (field (name ".CHECKED PCB") "RF, used by MM")
        (field (name ".CHECKED SCH") "MM")
      )
      (libsource (lib "Integrated_Library_RF_FEB_2012") (part "MAX9867ETJ+"))
    )
    (comp (ref "U6")
      (value "PCA9306DCTR")
      (footprint "DCT_8")
      (description "IC VOLT-LEVEL TRANSLATOR SM8")
      (fields
        (field (name "MANUFACTURER") "Texas Instruments")
        (field (name ".CREATOR") "MM")
        (field (name ".CHECKED PCB") "MM")
        (field (name ".CHECKED SCH") "MM")
      )
      (libsource (lib "Integrated_Library_RF_FEB_2012") (part "PCA9306DCTR"))
    )
    (comp (ref "Y1")
      (value "12.288MHz")
      (footprint "ASFLMB")
      (description "OSC MEMS 12.288 MHZ SMD")
      (fields
        (field (name "MANUFACTURER") "Abracon Corporation")
        (field (name "MANUFACTURER PART NUMBER") "ASFLMB-12.288MHZ-LR-T")
        (field (name ".CREATOR") "MM")
        (field (name ".CHECKED PCB") "MM")
        (field (name ".CHECKED SCH") "MM")
      )
      (libsource (lib "Integrated_Library_RF_FEB_2012") (part "ASFLMB-12.288MHZ-LR-T"))
    )
  )
  (nets
    (net (code "1") (name "+1V5") (class "Default")
      (node (ref "FB2") (pin "2") (pinfunction "2_2") (pintype "passive"))
    )
    (net (code "2") (name "+1V8_AUDIO2") (class "Default")
      (node (ref "C35") (pin "1") (pinfunction "1_1") (pintype "passive"))
      (node (ref "FB19") (pin "1") (pinfunction "1_1") (pintype "passive"))
      (node (ref "FB23") (pin "2") (pinfunction "2_2") (pintype "passive"))
      (node (ref "FB24") (pin "1") (pinfunction "1_1") (pintype "passive"))
      (node (ref "FB25") (pin "2") (pinfunction "2_2") (pintype "passive"))
      (node (ref "R116") (pin "2") (pinfunction "2_2") (pintype "passive"))
      (node (ref "R26") (pin "2") (pinfunction "2_2") (pintype "passive"))
      (node (ref "R29") (pin "2") (pinfunction "2_2") (pintype "passive"))
      (node (ref "R30") (pin "2") (pinfunction "2_2") (pintype "passive"))
      (node (ref "TP4") (pin "1") (pinfunction "1_1") (pintype "passive"))
      (node (ref "U3") (pin "10") (pinfunction "OUT_2_10") (pintype "passive"))
      (node (ref "U3") (pin "9") (pinfunction "OUT_1_9") (pintype "passive"))
      (node (ref "U6") (pin "2") (pinfunction "VREF1_2") (pintype "passive"))
    )
    (net (code "3") (name "+3V3") (class "Default")
      (node (ref "C33") (pin "1") (pinfunction "1_1") (pintype "passive"))
      (node (ref "C34") (pin "1") (pinfunction "1_1") (pintype "passive"))
      (node (ref "D6") (pin "2") (pinfunction "ANODE_2") (pintype "passive"))
      (node (ref "FB3") (pin "1") (pinfunction "1_1") (pintype "passive"))
      (node (ref "R150") (pin "2") (pinfunction "2_2") (pintype "passive"))
      (node (ref "R17") (pin "2") (pinfunction "2_2") (pintype "passive"))
      (node (ref "U3") (pin "1") (pinfunction "IN_1_1") (pintype "passive"))
      (node (ref "U3") (pin "2") (pinfunction "IN_2_2") (pintype "passive"))
      (node (ref "U3") (pin "4") (pinfunction "BIAS_4") (pintype "passive"))
    )
    (net (code "4") (name "+5V") (class "Default")
      (node (ref "FB4") (pin "1") (pinfunction "1_1") (pintype "passive"))
    )
    (net (code "5") (name "+5V_AUDIO1") (class "Default")
      (node (ref "C37") (pin "1") (pinfunction "1_1") (pintype "passive"))
      (node (ref "C38") (pin "1") (pinfunction "1_1") (pintype "passive"))
      (node (ref "C39") (pin "1") (pinfunction "1_1") (pintype "passive"))
      (node (ref "C40") (pin "1") (pinfunction "1_1") (pintype "passive"))
      (node (ref "C41") (pin "1") (pinfunction "1_1") (pintype "passive"))
      (node (ref "C42") (pin "1") (pinfunction "1_1") (pintype "passive"))
      (node (ref "C43") (pin "1") (pinfunction "1_1") (pintype "passive"))
      (node (ref "FB4") (pin "2") (pinfunction "2_2") (pintype "passive"))
      (node (ref "R31") (pin "2") (pinfunction "2_2") (pintype "passive"))
      (node (ref "R33") (pin "2") (pinfunction "2_2") (pintype "passive"))
      (node (ref "U4") (pin "17") (pinfunction "HPVDD_17") (pintype "passive"))
      (node (ref "U4") (pin "18") (pinfunction "SPVDD_2_18") (pintype "passive"))
      (node (ref "U4") (pin "30") (pinfunction "VDD_30") (pintype "passive"))
      (node (ref "U4") (pin "8") (pinfunction "SPVDD_1_8") (pintype "passive"))
      (node (ref "U4") (pin "9") (pinfunction "CPVDD_9") (pintype "passive"))
    )
    (net (code "6") (name "/+1V5_MPCIE2") (class "Default")
      (node (ref "C29") (pin "1") (pinfunction "1_1") (pintype "passive"))
      (node (ref "C30") (pin "1") (pinfunction "1_1") (pintype "passive"))
      (node (ref "C31") (pin "1") (pinfunction "1_1") (pintype "passive"))
      (node (ref "C32") (pin "1") (pinfunction "1_1") (pintype "passive"))
      (node (ref "FB2") (pin "1") (pinfunction "1_1") (pintype "passive"))
      (node (ref "J9") (pin "28") (pinfunction "1.5V_2_28") (pintype "passive"))
      (node (ref "J9") (pin "48") (pinfunction "1.5V_3_48") (pintype "passive"))
      (node (ref "J9") (pin "6") (pinfunction "1.5V_1_6") (pintype "passive"))
    )
    (net (code "7") (name "/+1V8_OSC") (class "Default")
      (node (ref "C49") (pin "1") (pinfunction "1_1") (pintype "passive"))
      (node (ref "FB24") (pin "2") (pinfunction "2_2") (pintype "passive"))
      (node (ref "Y1") (pin "1") (pinfunction "~{STB}_1") (pintype "passive"))
      (node (ref "Y1") (pin "4") (pinfunction "VDD_4") (pintype "passive"))
    )
    (net (code "8") (name "/+3V3_MPCIE2") (class "Default")
      (node (ref "C205") (pin "1") (pinfunction "1_1") (pintype "passive"))
      (node (ref "C206") (pin "1") (pinfunction "1_1") (pintype "passive"))
      (node (ref "C217") (pin "1") (pinfunction "1_1") (pintype "passive"))
      (node (ref "C218") (pin "1") (pinfunction "1_1") (pintype "passive"))
      (node (ref "C24") (pin "1") (pinfunction "1_1") (pintype "passive"))
      (node (ref "C25") (pin "1") (pinfunction "1_1") (pintype "passive"))
      (node (ref "C26") (pin "1") (pinfunction "1_1") (pintype "passive"))
      (node (ref "C27") (pin "1") (pinfunction "1_1") (pintype "passive"))
      (node (ref "FB3") (pin "2") (pinfunction "2_2") (pintype "passive"))
      (node (ref "J9") (pin "2") (pinfunction "3.3V_1_2") (pintype "passive"))
      (node (ref "J9") (pin "24") (pinfunction "+3.3Vaux_24") (pintype "passive"))
      (node (ref "J9") (pin "39") (pinfunction "Reserved_4_39") (pintype "passive"))
      (node (ref "J9") (pin "41") (pinfunction "Reserved_5_41") (pintype "passive"))
      (node (ref "J9") (pin "52") (pinfunction "3.3V_2_52") (pintype "passive"))
    )
    (net (code "9") (name "/+AUD2_AVDD") (class "Default")
      (node (ref "C45") (pin "1") (pinfunction "1_1") (pintype "passive"))
      (node (ref "FB23") (pin "1") (pinfunction "1_1") (pintype "passive"))
      (node (ref "U5") (pin "5") (pinfunction "AVDD_5") (pintype "passive"))
    )
    (net (code "10") (name "/+AUD2_DVDD") (class "Default")
      (node (ref "C44") (pin "1") (pinfunction "1_1") (pintype "passive"))
      (node (ref "C50") (pin "1") (pinfunction "1_1") (pintype "passive"))
      (node (ref "FB19") (pin "2") (pinfunction "2_2") (pintype "passive"))
      (node (ref "U5") (pin "26") (pinfunction "DVDDIO_26") (pintype "passive"))
      (node (ref "U5") (pin "32") (pinfunction "DVDD_32") (pintype "passive"))
    )
    (net (code "11") (name "/+AUD2_PVDD") (class "Default")
      (node (ref "C51") (pin "1") (pinfunction "1_1") (pintype "passive"))
      (node (ref "FB25") (pin "1") (pinfunction "1_1") (pintype "passive"))
      (node (ref "U5") (pin "23") (pinfunction "PVDD_23") (pintype "passive"))
    )
    (net (code "12") (name "/+MPCIE2_SIM_PWR") (class "Default")
      (node (ref "C28") (pin "1") (pinfunction "1_1") (pintype "passive"))
      (node (ref "D5") (pin "3") (pinfunction "3_3") (pintype "passive"))
      (node (ref "J7") (pin "C1") (pinfunction "VCC_C1") (pintype "passive"))
      (node (ref "J9") (pin "8") (pinfunction "UIM_PWR_8") (pintype "passive"))
    )
    (net (code "13") (name "/+MPCIE2_SIM_VPP") (class "Default")
      (node (ref "C106") (pin "1") (pinfunction "1_1") (pintype "passive"))
      (node (ref "J7") (pin "C6") (pinfunction "VPP_C6") (pintype "passive"))
      (node (ref "J9") (pin "16") (pinfunction "UIM_VPP_16") (pintype "passive"))
    )
    (net (code "14") (name "/AMP_BYPASS") (class "Default")
      (node (ref "C67") (pin "2") (pinfunction "2_2") (pintype "passive"))
      (node (ref "U4") (pin "24") (pinfunction "BYPASS_24") (pintype "passive"))
    )
    (net (code "15") (name "/AMP_C1N") (class "Default")
      (node (ref "C66") (pin "1") (pinfunction "1_1") (pintype "passive"))
      (node (ref "U4") (pin "12") (pinfunction "C1N_12") (pintype "passive"))
    )
    (net (code "16") (name "/AMP_C1P") (class "Default")
      (node (ref "C66") (pin "2") (pinfunction "2_2") (pintype "passive"))
      (node (ref "U4") (pin "10") (pinfunction "C1P_10") (pintype "passive"))
    )
    (net (code "17") (name "/AMP_GAIN") (class "Default")
      (node (ref "R33") (pin "1") (pinfunction "1_1") (pintype "passive"))
      (node (ref "R35") (pin "2") (pinfunction "2_2") (pintype "passive"))
      (node (ref "U4") (pin "31") (pinfunction "GAIN0_31") (pintype "passive"))
      (node (ref "U4") (pin "32") (pinfunction "GAIN1_32") (pintype "passive"))
    )
    (net (code "18") (name "/AMP_HP_EN") (class "Default")
      (node (ref "R31") (pin "1") (pinfunction "1_1") (pintype "passive"))
      (node (ref "U4") (pin "22") (pinfunction "HP_EN_22") (pintype "passive"))
    )
    (net (code "19") (name "/AMP_PVSS") (class "Default")
      (node (ref "C58") (pin "1") (pinfunction "1_1") (pintype "passive"))
      (node (ref "U4") (pin "13") (pinfunction "CPVSS_13") (pintype "passive"))
      (node (ref "U4") (pin "14") (pinfunction "HPVSS_14") (pintype "passive"))
    )
    (net (code "20") (name "/AMP_REG_EN") (class "Default")
      (node (ref "R32") (pin "2") (pinfunction "2_2") (pintype "passive"))
      (node (ref "U4") (pin "25") (pinfunction "REG_EN_25") (pintype "passive"))
    )
    (net (code "21") (name "/AMP_REG_OUT") (class "Default")
      (node (ref "C68") (pin "2") (pinfunction "2_2") (pintype "passive"))
      (node (ref "U4") (pin "29") (pinfunction "REG_OUT_29") (pintype "passive"))
    )
    (net (code "22") (name "/AMP_SPKR_ENn") (class "Default")
      (node (ref "R34") (pin "2") (pinfunction "2_2") (pintype "passive"))
      (node (ref "U4") (pin "23") (pinfunction "~{SPKR_EN}_23") (pintype "passive"))
    )
    (net (code "23") (name "/AUD2_AUX") (class "Default")
      (node (ref "TP5") (pin "1") (pinfunction "1_1") (pintype "passive"))
      (node (ref "U5") (pin "17") (pinfunction "JACKSNS/AUX_17") (pintype "passive"))
    )
    (net (code "24") (name "/AUD2_FIL_MIC_IN") (class "Default")
      (node (ref "C54") (pin "1") (pinfunction "1_1") (pintype "passive"))
      (node (ref "FB5") (pin "2") (pinfunction "2_2") (pintype "passive"))
      (node (ref "J11") (pin "1") (pinfunction "1_1") (pintype "passive"))
    )
    (net (code "25") (name "/AUD2_I2C2_SCL") (class "Default")
      (node (ref "R30") (pin "1") (pinfunction "1_1") (pintype "passive"))
      (node (ref "U5") (pin "2") (pinfunction "SCL_2") (pintype "passive"))
      (node (ref "U6") (pin "3") (pinfunction "SCL1_3") (pintype "passive"))
    )
    (net (code "26") (name "/AUD2_I2C2_SDA") (class "Default")
      (node (ref "R29") (pin "1") (pinfunction "1_1") (pintype "passive"))
      (node (ref "U5") (pin "3") (pinfunction "SDA_3") (pintype "passive"))
      (node (ref "U6") (pin "4") (pinfunction "SDA1_4") (pintype "passive"))
    )
    (net (code "27") (name "/AUD2_IRQ") (class "Default")
      (node (ref "R116") (pin "1") (pinfunction "1_1") (pintype "passive"))
      (node (ref "U5") (pin "4") (pinfunction "~{IRQ}_4") (pintype "passive"))
    )
    (net (code "28") (name "/AUD2_MIC_BIAS") (class "Default")
      (node (ref "C46") (pin "1") (pinfunction "1_1") (pintype "passive"))
      (node (ref "R28") (pin "2") (pinfunction "2_2") (pintype "passive"))
      (node (ref "U5") (pin "10") (pinfunction "MICBIAS_10") (pintype "passive"))
    )
    (net (code "29") (name "/AUD2_MIC_C_L") (class "Default")
      (node (ref "C65") (pin "2") (pinfunction "2_2") (pintype "passive"))
      (node (ref "U5") (pin "11") (pinfunction "MICLN/DIGMICCLK_11") (pintype "passive"))
    )
    (net (code "30") (name "/AUD2_MIC_C_R") (class "Default")
      (node (ref "C64") (pin "2") (pinfunction "2_2") (pintype "passive"))
      (node (ref "U5") (pin "14") (pinfunction "MICRN_14") (pintype "passive"))
    )
    (net (code "31") (name "/AUD2_MIC_IN") (class "Default")
      (node (ref "C48") (pin "2") (pinfunction "2_2") (pintype "passive"))
      (node (ref "C53") (pin "2") (pinfunction "2_2") (pintype "passive"))
      (node (ref "FB5") (pin "1") (pinfunction "1_1") (pintype "passive"))
      (node (ref "R28") (pin "1") (pinfunction "1_1") (pintype "passive"))
    )
    (net (code "32") (name "/AUD2_MIC_IN_L") (class "Default")
      (node (ref "C48") (pin "1") (pinfunction "1_1") (pintype "passive"))
      (node (ref "U5") (pin "12") (pinfunction "MICLP/DIGMICDATA_12") (pintype "passive"))
    )
    (net (code "33") (name "/AUD2_MIC_IN_R") (class "Default")
      (node (ref "C53") (pin "1") (pinfunction "1_1") (pintype "passive"))
      (node (ref "U5") (pin "13") (pinfunction "MICRP_13") (pintype "passive"))
    )
    (net (code "34") (name "/AUD2_PREG") (class "Default")
      (node (ref "C61") (pin "1") (pinfunction "1_1") (pintype "passive"))
      (node (ref "U5") (pin "7") (pinfunction "PREG_7") (pintype "passive"))
    )
    (net (code "35") (name "/AUD2_REF") (class "Default")
      (node (ref "C62") (pin "1") (pinfunction "1_1") (pintype "passive"))
      (node (ref "U5") (pin "6") (pinfunction "REF_6") (pintype "passive"))
    )
    (net (code "36") (name "/AUD2_REG") (class "Default")
      (node (ref "C63") (pin "1") (pinfunction "1_1") (pintype "passive"))
      (node (ref "U5") (pin "8") (pinfunction "REG_8") (pintype "passive"))
    )
    (net (code "37") (name "/BUF_SYS_RSTn") (class "Default")
      (node (ref "J9") (pin "22") (pinfunction "PERST#_22") (pintype "passive"))
    )
    (net (code "38") (name "/CPU_INT") (class "Default")
      (node (ref "J9") (pin "1") (pinfunction "WAKE#_1") (pintype "passive"))
    )
    (net (code "39") (name "/FB_+1V8_AUDIO2") (class "Default")
      (node (ref "R26") (pin "1") (pinfunction "1_1") (pintype "passive"))
      (node (ref "R27") (pin "2") (pinfunction "2_2") (pintype "passive"))
      (node (ref "U3") (pin "8") (pinfunction "FB_8") (pintype "passive"))
    )
    (net (code "40") (name "/HP_AMP_OUTL") (class "Default")
      (node (ref "U4") (pin "16") (pinfunction "HP_OUTL_16") (pintype "passive"))
    )
    (net (code "41") (name "/HP_AMP_OUTR") (class "Default")
      (node (ref "U4") (pin "15") (pinfunction "HP_OUTR_15") (pintype "passive"))
    )
    (net (code "42") (name "/HP_INL") (class "Default")
      (node (ref "U4") (pin "27") (pinfunction "HP_INL_27") (pintype "passive"))
    )
    (net (code "43") (name "/HP_INR") (class "Default")
      (node (ref "U4") (pin "26") (pinfunction "HP_INR_26") (pintype "passive"))
    )
    (net (code "44") (name "/I2C2_SCL") (class "Default")
      (node (ref "J9") (pin "30") (pinfunction "SMB_CLK_30") (pintype "passive"))
      (node (ref "U6") (pin "6") (pinfunction "SCL2_6") (pintype "passive"))
    )
    (net (code "45") (name "/I2C2_SDA") (class "Default")
      (node (ref "J9") (pin "32") (pinfunction "SMB_DATA_32") (pintype "passive"))
      (node (ref "U6") (pin "5") (pinfunction "SDA2_5") (pintype "passive"))
    )
    (net (code "46") (name "/I2C2_VREF2") (class "Default")
      (node (ref "C57") (pin "1") (pinfunction "1_1") (pintype "passive"))
      (node (ref "R17") (pin "1") (pinfunction "1_1") (pintype "passive"))
      (node (ref "U6") (pin "7") (pinfunction "VREF2_7") (pintype "passive"))
      (node (ref "U6") (pin "8") (pinfunction "EN_8") (pintype "passive"))
    )
    (net (code "47") (name "/LED_MPCIE2_WWAN") (class "Default")
      (node (ref "J9") (pin "42") (pinfunction "LED_WWAN#_42") (pintype "passive"))
      (node (ref "R25") (pin "1") (pinfunction "1_1") (pintype "passive"))
    )
    (net (code "48") (name "/LINE_IN_C_L") (class "Default")
      (node (ref "C59") (pin "2") (pinfunction "2_2") (pintype "passive"))
      (node (ref "J13") (pin "3") (pinfunction "3_3") (pintype "passive"))
    )
    (net (code "49") (name "/LINE_IN_C_R") (class "Default")
      (node (ref "C60") (pin "2") (pinfunction "2_2") (pintype "passive"))
      (node (ref "J13") (pin "1") (pinfunction "1_1") (pintype "passive"))
    )
    (net (code "50") (name "/LINE_IN_L") (class "Default")
      (node (ref "C59") (pin "1") (pinfunction "1_1") (pintype "passive"))
      (node (ref "U5") (pin "15") (pinfunction "LINL_15") (pintype "passive"))
    )
    (net (code "51") (name "/LINE_IN_R") (class "Default")
      (node (ref "C60") (pin "1") (pinfunction "1_1") (pintype "passive"))
      (node (ref "U5") (pin "16") (pinfunction "LINR_16") (pintype "passive"))
    )
    (net (code "52") (name "/MODEM_LOUT+") (class "Default")
      (node (ref "C210") (pin "2") (pinfunction "2_2") (pintype "passive"))
      (node (ref "J10") (pin "1") (pinfunction "1_1") (pintype "passive"))
      (node (ref "U4") (pin "6") (pinfunction "LOUT+_6") (pintype "passive"))
    )
    (net (code "53") (name "/MODEM_LOUT-") (class "Default")
      (node (ref "J10") (pin "2") (pinfunction "2_2") (pintype "passive"))
      (node (ref "R156") (pin "2") (pinfunction "2_2") (pintype "passive"))
      (node (ref "U4") (pin "7") (pinfunction "LOUT_7") (pintype "passive"))
    )
    (net (code "54") (name "/MODEM_ROUT+") (class "Default")
      (node (ref "C212") (pin "2") (pinfunction "2_2") (pintype "passive"))
      (node (ref "J12") (pin "1") (pinfunction "1_1") (pintype "passive"))
      (node (ref "U4") (pin "20") (pinfunction "ROUT+_20") (pintype "passive"))
    )
    (net (code "55") (name "/MODEM_ROUT-") (class "Default")
      (node (ref "J12") (pin "2") (pinfunction "2_2") (pintype "passive"))
      (node (ref "R155") (pin "2") (pinfunction "2_2") (pintype "passive"))
      (node (ref "U4") (pin "19") (pinfunction "ROUT_19") (pintype "passive"))
    )
    (net (code "56") (name "/MPCIE2_12M_CLK") (class "Default")
      (node (ref "U5") (pin "31") (pinfunction "MCLK_31") (pintype "passive"))
      (node (ref "Y1") (pin "3") (pinfunction "OUT_3") (pintype "passive"))
    )
    (net (code "57") (name "/MPCIE2_PCM_CLK") (class "Default")
      (node (ref "J9") (pin "45") (pinfunction "Reserved_7_45") (pintype "passive"))
      (node (ref "U5") (pin "30") (pinfunction "BCLK_30") (pintype "passive"))
    )
    (net (code "58") (name "/MPCIE2_PCM_RX") (class "Default")
      (node (ref "J9") (pin "47") (pinfunction "Reserved_8_47") (pintype "passive"))
      (node (ref "U5") (pin "27") (pinfunction "SDOUT_27") (pintype "passive"))
    )
    (net (code "59") (name "/MPCIE2_PCM_SYNC") (class "Default")
      (node (ref "J9") (pin "51") (pinfunction "Reserved_10_51") (pintype "passive"))
      (node (ref "U5") (pin "29") (pinfunction "LRCLK_29") (pintype "passive"))
    )
    (net (code "60") (name "/MPCIE2_PCM_TX") (class "Default")
      (node (ref "J9") (pin "49") (pinfunction "Reserved_9_49") (pintype "passive"))
      (node (ref "U5") (pin "28") (pinfunction "SDIN_28") (pintype "passive"))
    )
    (net (code "61") (name "/MPCIE2_SIM_CLK") (class "Default")
      (node (ref "D5") (pin "5") (pinfunction "5_5") (pintype "passive"))
      (node (ref "J7") (pin "C3") (pinfunction "CLK_C3") (pintype "passive"))
      (node (ref "J9") (pin "12") (pinfunction "UIM_CLK_12") (pintype "passive"))
    )
    (net (code "62") (name "/MPCIE2_SIM_DATA") (class "Default")
      (node (ref "D5") (pin "4") (pinfunction "4_4") (pintype "passive"))
      (node (ref "J7") (pin "C7") (pinfunction "I/O_C7") (pintype "passive"))
      (node (ref "J9") (pin "10") (pinfunction "UIM_DATA_10") (pintype "passive"))
    )
    (net (code "63") (name "/MPCIE2_SIM_RST") (class "Default")
      (node (ref "D5") (pin "1") (pinfunction "1_1") (pintype "passive"))
      (node (ref "J7") (pin "C2") (pinfunction "RESET_C2") (pintype "passive"))
      (node (ref "J9") (pin "14") (pinfunction "UIM_RESET_14") (pintype "passive"))
    )
    (net (code "64") (name "/MPCIE2_WDISn") (class "Default")
      (node (ref "J9") (pin "20") (pinfunction "W_DISABLE#_20") (pintype "passive"))
      (node (ref "R150") (pin "1") (pinfunction "1_1") (pintype "passive"))
    )
    (net (code "65") (name "/POK_1V5") (class "Default")
      (node (ref "U3") (pin "5") (pinfunction "EN_5") (pintype "passive"))
    )
    (net (code "66") (name "/POKn") (class "Default")
      (node (ref "U3") (pin "3") (pinfunction "PG_3") (pintype "passive"))
    )
    (net (code "67") (name "/SPKR_C_LOUT+") (class "Default")
      (node (ref "C52") (pin "2") (pinfunction "2_2") (pintype "passive"))
      (node (ref "U4") (pin "3") (pinfunction "SPKR_LIN+_3") (pintype "passive"))
    )
    (net (code "68") (name "/SPKR_C_LOUT-") (class "Default")
      (node (ref "C47") (pin "2") (pinfunction "2_2") (pintype "passive"))
      (node (ref "U4") (pin "4") (pinfunction "SPKR_LIN_4") (pintype "passive"))
    )
    (net (code "69") (name "/SPKR_C_ROUT+") (class "Default")
      (node (ref "C56") (pin "2") (pinfunction "2_2") (pintype "passive"))
      (node (ref "U4") (pin "2") (pinfunction "SPKR_RIN+_2") (pintype "passive"))
    )
    (net (code "70") (name "/SPKR_C_ROUT-") (class "Default")
      (node (ref "C55") (pin "2") (pinfunction "2_2") (pintype "passive"))
      (node (ref "U4") (pin "1") (pinfunction "SPKR_RIN_1") (pintype "passive"))
    )
    (net (code "71") (name "/SPKR_LOUT+") (class "Default")
      (node (ref "C210") (pin "1") (pinfunction "1_1") (pintype "passive"))
      (node (ref "C52") (pin "1") (pinfunction "1_1") (pintype "passive"))
      (node (ref "U5") (pin "22") (pinfunction "LOUTP_22") (pintype "passive"))
    )
    (net (code "72") (name "/SPKR_LOUT-") (class "Default")
      (node (ref "C209") (pin "2") (pinfunction "2_2") (pintype "passive"))
      (node (ref "C47") (pin "1") (pinfunction "1_1") (pintype "passive"))
      (node (ref "U5") (pin "21") (pinfunction "LOUTN_21") (pintype "passive"))
    )
    (net (code "73") (name "/SPKR_ROUT+") (class "Default")
      (node (ref "C212") (pin "1") (pinfunction "1_1") (pintype "passive"))
      (node (ref "C56") (pin "1") (pinfunction "1_1") (pintype "passive"))
      (node (ref "U5") (pin "19") (pinfunction "ROUTP_19") (pintype "passive"))
    )
    (net (code "74") (name "/SPKR_ROUT-") (class "Default")
      (node (ref "C211") (pin "2") (pinfunction "2_2") (pintype "passive"))
      (node (ref "C55") (pin "1") (pinfunction "1_1") (pintype "passive"))
      (node (ref "U5") (pin "20") (pinfunction "ROUTN_20") (pintype "passive"))
    )
    (net (code "75") (name "/SS_+1V8_AUDIO2") (class "Default")
      (node (ref "C36") (pin "1") (pinfunction "1_1") (pintype "passive"))
      (node (ref "U3") (pin "7") (pinfunction "SS_7") (pintype "passive"))
    )
    (net (code "76") (name "/USB_MPCIE2_CON_N") (class "Default")
      (node (ref "J9") (pin "36") (pinfunction "USB_D-_36") (pintype "passive"))
      (node (ref "L2") (pin "1") (pinfunction "1_1") (pintype "passive"))
    )
    (net (code "77") (name "/USB_MPCIE2_CON_P") (class "Default")
      (node (ref "J9") (pin "38") (pinfunction "USB_D+_38") (pintype "passive"))
      (node (ref "L2") (pin "2") (pinfunction "2_2") (pintype "passive"))
    )
    (net (code "78") (name "/USB_MPCIE2_N") (class "Default")
      (node (ref "L2") (pin "4") (pinfunction "4_4") (pintype "passive"))
    )
    (net (code "79") (name "/USB_MPCIE2_P") (class "Default")
      (node (ref "L2") (pin "3") (pinfunction "3_3") (pintype "passive"))
    )
    (net (code "80") (name "GND") (class "Default")
      (node (ref "C106") (pin "2") (pinfunction "2_2") (pintype "passive"))
      (node (ref "C205") (pin "2") (pinfunction "2_2") (pintype "passive"))
      (node (ref "C206") (pin "2") (pinfunction "2_2") (pintype "passive"))
      (node (ref "C209") (pin "1") (pinfunction "1_1") (pintype "passive"))
      (node (ref "C211") (pin "1") (pinfunction "1_1") (pintype "passive"))
      (node (ref "C217") (pin "2") (pinfunction "2_2") (pintype "passive"))
      (node (ref "C218") (pin "2") (pinfunction "2_2") (pintype "passive"))
      (node (ref "C24") (pin "2") (pinfunction "2_2") (pintype "passive"))
      (node (ref "C25") (pin "2") (pinfunction "2_2") (pintype "passive"))
      (node (ref "C26") (pin "2") (pinfunction "2_2") (pintype "passive"))
      (node (ref "C27") (pin "2") (pinfunction "2_2") (pintype "passive"))
      (node (ref "C28") (pin "2") (pinfunction "2_2") (pintype "passive"))
      (node (ref "C29") (pin "2") (pinfunction "2_2") (pintype "passive"))
      (node (ref "C30") (pin "2") (pinfunction "2_2") (pintype "passive"))
      (node (ref "C31") (pin "2") (pinfunction "2_2") (pintype "passive"))
      (node (ref "C32") (pin "2") (pinfunction "2_2") (pintype "passive"))
      (node (ref "C33") (pin "2") (pinfunction "2_2") (pintype "passive"))
      (node (ref "C34") (pin "2") (pinfunction "2_2") (pintype "passive"))
      (node (ref "C35") (pin "2") (pinfunction "2_2") (pintype "passive"))
      (node (ref "C36") (pin "2") (pinfunction "2_2") (pintype "passive"))
      (node (ref "C37") (pin "2") (pinfunction "2_2") (pintype "passive"))
      (node (ref "C38") (pin "2") (pinfunction "2_2") (pintype "passive"))
      (node (ref "C39") (pin "2") (pinfunction "2_2") (pintype "passive"))
      (node (ref "C40") (pin "2") (pinfunction "2_2") (pintype "passive"))
      (node (ref "C41") (pin "2") (pinfunction "2_2") (pintype "passive"))
      (node (ref "C42") (pin "2") (pinfunction "2_2") (pintype "passive"))
      (node (ref "C43") (pin "2") (pinfunction "2_2") (pintype "passive"))
      (node (ref "C44") (pin "2") (pinfunction "2_2") (pintype "passive"))
      (node (ref "C45") (pin "2") (pinfunction "2_2") (pintype "passive"))
      (node (ref "C46") (pin "2") (pinfunction "2_2") (pintype "passive"))
      (node (ref "C49") (pin "2") (pinfunction "2_2") (pintype "passive"))
      (node (ref "C50") (pin "2") (pinfunction "2_2") (pintype "passive"))
      (node (ref "C51") (pin "2") (pinfunction "2_2") (pintype "passive"))
      (node (ref "C54") (pin "2") (pinfunction "2_2") (pintype "passive"))
      (node (ref "C57") (pin "2") (pinfunction "2_2") (pintype "passive"))
      (node (ref "C58") (pin "2") (pinfunction "2_2") (pintype "passive"))
      (node (ref "C61") (pin "2") (pinfunction "2_2") (pintype "passive"))
      (node (ref "C62") (pin "2") (pinfunction "2_2") (pintype "passive"))
      (node (ref "C63") (pin "2") (pinfunction "2_2") (pintype "passive"))
      (node (ref "C64") (pin "1") (pinfunction "1_1") (pintype "passive"))
      (node (ref "C65") (pin "1") (pinfunction "1_1") (pintype "passive"))
      (node (ref "C67") (pin "1") (pinfunction "1_1") (pintype "passive"))
      (node (ref "C68") (pin "1") (pinfunction "1_1") (pintype "passive"))
      (node (ref "D5") (pin "2") (pinfunction "2_2") (pintype "passive"))
      (node (ref "J11") (pin "2") (pinfunction "2_2") (pintype "passive"))
      (node (ref "J13") (pin "2") (pinfunction "2_2") (pintype "passive"))
      (node (ref "J7") (pin "1") (pinfunction "H1_1") (pintype "passive"))
      (node (ref "J7") (pin "2") (pinfunction "H2_2") (pintype "passive"))
      (node (ref "J7") (pin "C5") (pinfunction "GND_C5") (pintype "passive"))
      (node (ref "J8") (pin "1") (pinfunction "1_1") (pintype "passive"))
      (node (ref "J8") (pin "2") (pinfunction "2_2") (pintype "passive"))
      (node (ref "J8") (pin "3") (pinfunction "3_3") (pintype "passive"))
      (node (ref "J8") (pin "4") (pinfunction "4_4") (pintype "passive"))
      (node (ref "J8") (pin "5") (pinfunction "5_5") (pintype "passive"))
      (node (ref "J8") (pin "6") (pinfunction "6_6") (pintype "passive"))
      (node (ref "J9") (pin "15") (pinfunction "GND_2_15") (pintype "passive"))
      (node (ref "J9") (pin "18") (pinfunction "GND_8_18") (pintype "passive"))
      (node (ref "J9") (pin "21") (pinfunction "GND_3_21") (pintype "passive"))
      (node (ref "J9") (pin "26") (pinfunction "GND_9_26") (pintype "passive"))
      (node (ref "J9") (pin "27") (pinfunction "GND_4_27") (pintype "passive"))
      (node (ref "J9") (pin "29") (pinfunction "GND_5_29") (pintype "passive"))
      (node (ref "J9") (pin "34") (pinfunction "GND_10_34") (pintype "passive"))
      (node (ref "J9") (pin "35") (pinfunction "GND_6_35") (pintype "passive"))
      (node (ref "J9") (pin "37") (pinfunction "Reserved_3_37") (pintype "passive"))
      (node (ref "J9") (pin "4") (pinfunction "GND_7_4") (pintype "passive"))
      (node (ref "J9") (pin "40") (pinfunction "GND_11_40") (pintype "passive"))
      (node (ref "J9") (pin "43") (pinfunction "Reserved_6_43") (pintype "passive"))
      (node (ref "J9") (pin "50") (pinfunction "GND_12_50") (pintype "passive"))
      (node (ref "J9") (pin "53") (pinfunction "S1_53") (pintype "passive"))
      (node (ref "J9") (pin "54") (pinfunction "S2_54") (pintype "passive"))
      (node (ref "J9") (pin "9") (pinfunction "GND_1_9") (pintype "passive"))
      (node (ref "R155") (pin "1") (pinfunction "1_1") (pintype "passive"))
      (node (ref "R156") (pin "1") (pinfunction "1_1") (pintype "passive"))
      (node (ref "R27") (pin "1") (pinfunction "1_1") (pintype "passive"))
      (node (ref "R32") (pin "1") (pinfunction "1_1") (pintype "passive"))
      (node (ref "R34") (pin "1") (pinfunction "1_1") (pintype "passive"))
      (node (ref "R35") (pin "1") (pinfunction "1_1") (pintype "passive"))
      (node (ref "U3") (pin "11") (pinfunction "EPAD_1_11") (pintype "passive"))
      (node (ref "U3") (pin "12") (pinfunction "EPAD_2_12") (pintype "passive"))
      (node (ref "U3") (pin "13") (pinfunction "EPAD_3_13") (pintype "passive"))
      (node (ref "U3") (pin "14") (pinfunction "EPAD_4_14") (pintype "passive"))
      (node (ref "U3") (pin "15") (pinfunction "EPAD_5_15") (pintype "passive"))
      (node (ref "U3") (pin "6") (pinfunction "GND_6") (pintype "passive"))
      (node (ref "U4") (pin "11") (pinfunction "CPGND_11") (pintype "passive"))
      (node (ref "U4") (pin "21") (pinfunction "SPGND_2_21") (pintype "passive"))
      (node (ref "U4") (pin "28") (pinfunction "SGND_28") (pintype "passive"))
      (node (ref "U4") (pin "33") (pinfunction "EPAD_33") (pintype "passive"))
      (node (ref "U4") (pin "5") (pinfunction "SPGND_1_5") (pintype "passive"))
      (node (ref "U5") (pin "1") (pinfunction "DGND_1") (pintype "passive"))
      (node (ref "U5") (pin "18") (pinfunction "PGND_18") (pintype "passive"))
      (node (ref "U5") (pin "33") (pinfunction "EPAD_33") (pintype "passive"))
      (node (ref "U5") (pin "9") (pinfunction "AGND_9") (pintype "passive"))
      (node (ref "U6") (pin "1") (pinfunction "GND_1") (pintype "passive"))
      (node (ref "Y1") (pin "2") (pinfunction "GND_2") (pintype "passive"))
    )
    (net (code "81") (name "Net-(D6-cathode)") (class "Default")
      (node (ref "D6") (pin "1") (pinfunction "cathode_1") (pintype "passive"))
      (node (ref "R25") (pin "2") (pinfunction "2_2") (pintype "passive"))
    )
    (net (code "82") (name "unconnected-(J7-CD1-PadS1)") (class "Default")
      (node (ref "J7") (pin "S1") (pinfunction "CD1_S1") (pintype "passive+no_connect"))
    )
    (net (code "83") (name "unconnected-(J7-CD2-PadS2)") (class "Default")
      (node (ref "J7") (pin "S2") (pinfunction "CD2_S2") (pintype "passive+no_connect"))
    )
    (net (code "84") (name "unconnected-(J9-CLKREQ#-Pad7)") (class "Default")
      (node (ref "J9") (pin "7") (pinfunction "CLKREQ#_7") (pintype "passive+no_connect"))
    )
    (net (code "85") (name "unconnected-(J9-LED_WLAN#-Pad44)") (class "Default")
      (node (ref "J9") (pin "44") (pinfunction "LED_WLAN#_44") (pintype "passive+no_connect"))
    )
    (net (code "86") (name "unconnected-(J9-LED_WPAN#-Pad46)") (class "Default")
      (node (ref "J9") (pin "46") (pinfunction "LED_WPAN#_46") (pintype "passive+no_connect"))
    )
    (net (code "87") (name "unconnected-(J9-PERn0-Pad23)") (class "Default")
      (node (ref "J9") (pin "23") (pinfunction "PERn0_23") (pintype "passive+no_connect"))
    )
    (net (code "88") (name "unconnected-(J9-PERp0-Pad25)") (class "Default")
      (node (ref "J9") (pin "25") (pinfunction "PERp0_25") (pintype "passive+no_connect"))
    )
    (net (code "89") (name "unconnected-(J9-PETn0-Pad31)") (class "Default")
      (node (ref "J9") (pin "31") (pinfunction "PETn0_31") (pintype "passive+no_connect"))
    )
    (net (code "90") (name "unconnected-(J9-PETp0-Pad33)") (class "Default")
      (node (ref "J9") (pin "33") (pinfunction "PETp0_33") (pintype "passive+no_connect"))
    )
    (net (code "91") (name "unconnected-(J9-REFCLK+-Pad13)") (class "Default")
      (node (ref "J9") (pin "13") (pinfunction "REFCLK+_13") (pintype "passive+no_connect"))
    )
    (net (code "92") (name "unconnected-(J9-REFCLK--Pad11)") (class "Default")
      (node (ref "J9") (pin "11") (pinfunction "REFCLK-_11") (pintype "passive+no_connect"))
    )
    (net (code "93") (name "unconnected-(J9-Reserved_1-Pad3)") (class "Default")
      (node (ref "J9") (pin "3") (pinfunction "Reserved_1_3") (pintype "passive+no_connect"))
    )
    (net (code "94") (name "unconnected-(J9-Reserved_2-Pad5)") (class "Default")
      (node (ref "J9") (pin "5") (pinfunction "Reserved_2_5") (pintype "passive+no_connect"))
    )
    (net (code "95") (name "unconnected-(J9-Reserved{slash}UIM_C4-Pad19)") (class "Default")
      (node (ref "J9") (pin "19") (pinfunction "Reserved/UIM_C4_19") (pintype "passive+no_connect"))
    )
    (net (code "96") (name "unconnected-(J9-Reserved{slash}UIM_C8-Pad17)") (class "Default")
      (node (ref "J9") (pin "17") (pinfunction "Reserved/UIM_C8_17") (pintype "passive+no_connect"))
    )
    (net (code "97") (name "unconnected-(U5-NC_1-Pad24)") (class "Default")
      (node (ref "U5") (pin "24") (pinfunction "NC_1_24") (pintype "passive+no_connect"))
    )
    (net (code "98") (name "unconnected-(U5-NC_2-Pad25)") (class "Default")
      (node (ref "U5") (pin "25") (pinfunction "NC_2_25") (pintype "passive+no_connect"))
    )
  )
)
